# DSO_IO.net
KiCad netlist of a schematic drawn in Altium Designer
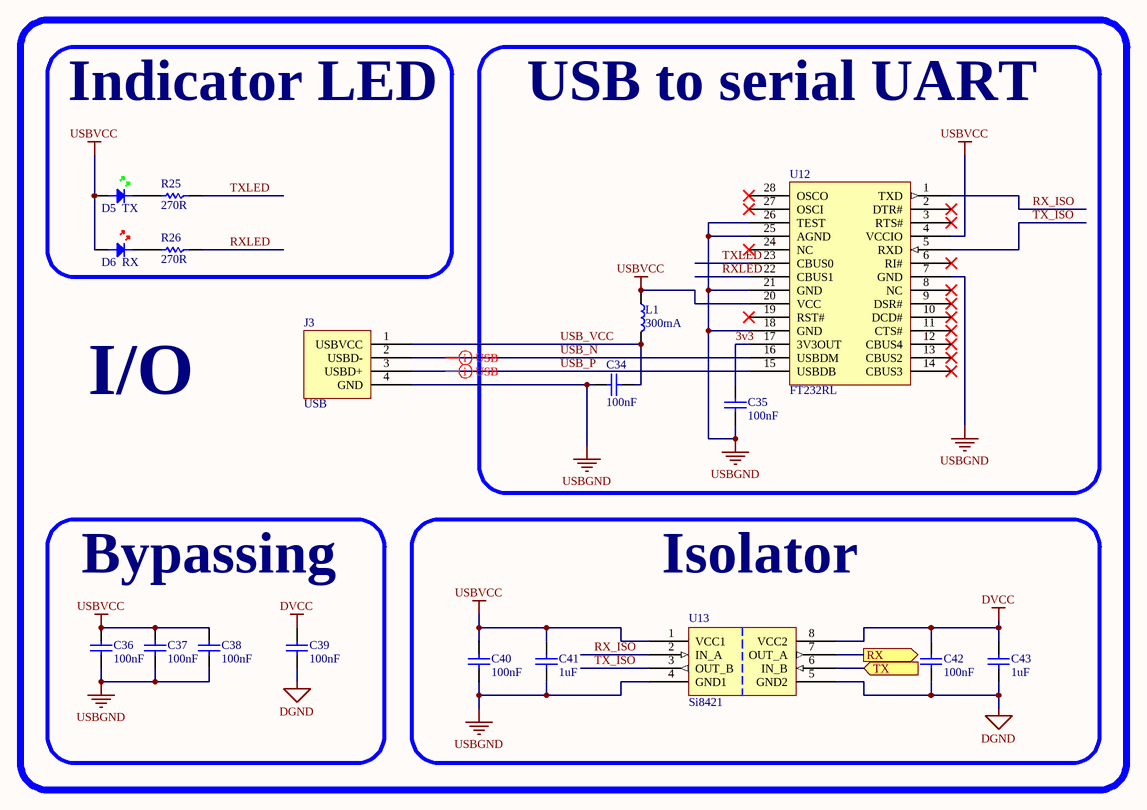
[diagram p0: DSO_IO.SchDoc]

(export (version "E")
  (design (tool "Eeschema 10.0.6"))
  (components
    (comp (ref "C34")
      (value "100nF")
      (footprint "0805C")
      (description "Capacitor")
      (fields (field (name "REVIEWED BY") "RM - 2018/08/05"))
      (libsource (lib "DSO") (part "C"))
    )
    (comp (ref "C35")
      (value "100nF")
      (footprint "0805C")
      (description "Capacitor")
      (fields (field (name "REVIEWED BY") "RM - 2018/08/05"))
      (libsource (lib "DSO") (part "C"))
    )
    (comp (ref "C36")
      (value "100nF")
      (footprint "0805C")
      (description "Capacitor")
      (fields (field (name "REVIEWED BY") "RM - 2018/08/05"))
      (libsource (lib "DSO") (part "C"))
    )
    (comp (ref "C37")
      (value "100nF")
      (footprint "0805C")
      (description "Capacitor")
      (fields (field (name "REVIEWED BY") "RM - 2018/08/05"))
      (libsource (lib "DSO") (part "C"))
    )
    (comp (ref "C38")
      (value "100nF")
      (footprint "0805C")
      (description "Capacitor")
      (fields (field (name "REVIEWED BY") "RM - 2018/08/05"))
      (libsource (lib "DSO") (part "C"))
    )
    (comp (ref "C39")
      (value "100nF")
      (footprint "0805C")
      (description "Capacitor")
      (fields (field (name "REVIEWED BY") "RM - 2018/08/05"))
      (libsource (lib "DSO") (part "C"))
    )
    (comp (ref "C40")
      (value "100nF")
      (footprint "0805C")
      (description "Capacitor")
      (fields (field (name "REVIEWED BY") "RM - 2018/08/05"))
      (libsource (lib "DSO") (part "C"))
    )
    (comp (ref "C41")
      (value "1uF")
      (footprint "0805C")
      (description "Capacitor")
      (fields (field (name "REVIEWED BY") "RM - 2018/08/05"))
      (libsource (lib "DSO") (part "C"))
    )
    (comp (ref "C42")
      (value "100nF")
      (footprint "0805C")
      (description "Capacitor")
      (fields (field (name "REVIEWED BY") "RM - 2018/08/05"))
      (libsource (lib "DSO") (part "C"))
    )
    (comp (ref "C43")
      (value "1uF")
      (footprint "0805C")
      (description "Capacitor")
      (fields (field (name "REVIEWED BY") "RM - 2018/08/05"))
      (libsource (lib "DSO") (part "C"))
    )
    (comp (ref "D5")
      (value "TX")
      (footprint "0805D-GREEN")
      (description "Light Emitting Diode")
      (fields (field (name "REVIEWED BY") "RM - 2018/08/05"))
      (libsource (lib "DSO") (part "LED GREEN"))
    )
    (comp (ref "D6")
      (value "RX")
      (footprint "0805D-RED")
      (description "Light Emitting Diode")
      (fields (field (name "REVIEWED BY") "RM - 2018/08/05"))
      (libsource (lib "DSO") (part "LED RED"))
    )
    (comp (ref "J3")
      (value "USB")
      (footprint "USBPLUG")
      (description "USB B Type Connector")
      (fields (field (name "REVIEWED BY") "RM - 2018/08/05"))
      (libsource (lib "DSO") (part "USBPLUG"))
    )
    (comp (ref "L1")
      (value "300mA")
      (footprint "0805")
      (description "Inductor")
      (fields (field (name "REVIEWED BY") "RM - 2018/08/05"))
      (libsource (lib "DSO") (part "I"))
    )
    (comp (ref "R25")
      (value "270R")
      (footprint "0805")
      (description "Resistor")
      (fields (field (name "REVIEWED BY") "RM - 2018/08/05"))
      (libsource (lib "DSO") (part "R"))
    )
    (comp (ref "R26")
      (value "270R")
      (footprint "0805")
      (description "Resistor")
      (fields (field (name "REVIEWED BY") "RM - 2018/08/05"))
      (libsource (lib "DSO") (part "R"))
    )
    (comp (ref "U12")
      (value "FT232RL")
      (footprint "SSOP-28")
      (description "USB to Serial bridge")
      (fields (field (name "REVIEWED BY") "RM - 2018/08/05"))
      (libsource (lib "DSO") (part "FT232RL"))
    )
    (comp (ref "U13")
      (value "Si8421")
      (footprint "SOIC-8")
      (description "Dual Channel Digital Isolator Both Ways")
      (fields (field (name "REVIEWED BY") "RM - 2018/08/05"))
      (libsource (lib "DSO") (part "Si8421"))
    )
  )
  (nets
    (net (code "1") (name "/3v3") (class "Default")
      (node (ref "C35") (pin "1") (pinfunction "1_1") (pintype "passive"))
      (node (ref "U12") (pin "17") (pinfunction "3V3OUT_17") (pintype "passive"))
    )
    (net (code "2") (name "/RX") (class "Default")
      (node (ref "U13") (pin "7") (pinfunction "OUT_A_7") (pintype "output"))
    )
    (net (code "3") (name "/RXLED") (class "Default")
      (node (ref "R26") (pin "1") (pintype "passive"))
      (node (ref "U12") (pin "22") (pinfunction "CBUS1_22") (pintype "passive"))
    )
    (net (code "4") (name "/RX_ISO") (class "Default")
      (node (ref "U12") (pin "1") (pinfunction "TXD_1") (pintype "output"))
      (node (ref "U13") (pin "2") (pinfunction "IN_A_2") (pintype "input"))
    )
    (net (code "5") (name "/TX") (class "Default")
      (node (ref "U13") (pin "6") (pinfunction "IN_B_6") (pintype "input"))
    )
    (net (code "6") (name "/TXLED") (class "Default")
      (node (ref "R25") (pin "1") (pintype "passive"))
      (node (ref "U12") (pin "23") (pinfunction "CBUS0_23") (pintype "passive"))
    )
    (net (code "7") (name "/TX_ISO") (class "Default")
      (node (ref "U12") (pin "5") (pinfunction "RXD_5") (pintype "input"))
      (node (ref "U13") (pin "3") (pinfunction "OUT_B_3") (pintype "output"))
    )
    (net (code "8") (name "/USB_N") (class "Default")
      (node (ref "J3") (pin "2") (pinfunction "USBD-_2") (pintype "passive"))
      (node (ref "U12") (pin "16") (pinfunction "USBDM_16") (pintype "passive"))
    )
    (net (code "9") (name "/USB_P") (class "Default")
      (node (ref "J3") (pin "3") (pinfunction "USBD+_3") (pintype "passive"))
      (node (ref "U12") (pin "15") (pinfunction "USBDB_15") (pintype "passive"))
    )
    (net (code "10") (name "/USB_VCC") (class "Default")
      (node (ref "C34") (pin "1") (pinfunction "1_1") (pintype "passive"))
      (node (ref "J3") (pin "1") (pinfunction "USBVCC_1") (pintype "passive"))
      (node (ref "L1") (pin "2") (pinfunction "2_2") (pintype "passive"))
    )
    (net (code "11") (name "DGND") (class "Default")
      (node (ref "C39") (pin "2") (pinfunction "2_2") (pintype "passive"))
      (node (ref "C42") (pin "2") (pinfunction "2_2") (pintype "passive"))
      (node (ref "C43") (pin "2") (pinfunction "2_2") (pintype "passive"))
      (node (ref "U13") (pin "5") (pinfunction "GND2_5") (pintype "passive"))
    )
    (net (code "12") (name "DVCC") (class "Default")
      (node (ref "C39") (pin "1") (pinfunction "1_1") (pintype "passive"))
      (node (ref "C42") (pin "1") (pinfunction "1_1") (pintype "passive"))
      (node (ref "C43") (pin "1") (pinfunction "1_1") (pintype "passive"))
      (node (ref "U13") (pin "8") (pinfunction "VCC2_8") (pintype "passive"))
    )
    (net (code "13") (name "Net-(D5-PadK)") (class "Default")
      (node (ref "D5") (pin "K") (pinfunction "K_K") (pintype "passive"))
      (node (ref "R25") (pin "2") (pintype "passive"))
    )
    (net (code "14") (name "Net-(D6-PadK)") (class "Default")
      (node (ref "D6") (pin "K") (pinfunction "K_K") (pintype "passive"))
      (node (ref "R26") (pin "2") (pintype "passive"))
    )
    (net (code "15") (name "USBGND") (class "Default")
      (node (ref "C34") (pin "2") (pinfunction "2_2") (pintype "passive"))
      (node (ref "C35") (pin "2") (pinfunction "2_2") (pintype "passive"))
      (node (ref "C36") (pin "2") (pinfunction "2_2") (pintype "passive"))
      (node (ref "C37") (pin "2") (pinfunction "2_2") (pintype "passive"))
      (node (ref "C38") (pin "2") (pinfunction "2_2") (pintype "passive"))
      (node (ref "C40") (pin "2") (pinfunction "2_2") (pintype "passive"))
      (node (ref "C41") (pin "2") (pinfunction "2_2") (pintype "passive"))
      (node (ref "J3") (pin "4") (pinfunction "GND_4") (pintype "passive"))
      (node (ref "U12") (pin "18") (pinfunction "GND_18") (pintype "passive"))
      (node (ref "U12") (pin "21") (pinfunction "GND_21") (pintype "passive"))
      (node (ref "U12") (pin "25") (pinfunction "AGND_25") (pintype "passive"))
      (node (ref "U12") (pin "26") (pinfunction "TEST_26") (pintype "passive"))
      (node (ref "U12") (pin "7") (pinfunction "GND_7") (pintype "passive"))
      (node (ref "U13") (pin "4") (pinfunction "GND1_4") (pintype "passive"))
    )
    (net (code "16") (name "USBVCC") (class "Default")
      (node (ref "C36") (pin "1") (pinfunction "1_1") (pintype "passive"))
      (node (ref "C37") (pin "1") (pinfunction "1_1") (pintype "passive"))
      (node (ref "C38") (pin "1") (pinfunction "1_1") (pintype "passive"))
      (node (ref "C40") (pin "1") (pinfunction "1_1") (pintype "passive"))
      (node (ref "C41") (pin "1") (pinfunction "1_1") (pintype "passive"))
      (node (ref "D5") (pin "A") (pinfunction "A_A") (pintype "passive"))
      (node (ref "D6") (pin "A") (pinfunction "A_A") (pintype "passive"))
      (node (ref "L1") (pin "1") (pinfunction "1_1") (pintype "passive"))
      (node (ref "U12") (pin "20") (pinfunction "VCC_20") (pintype "passive"))
      (node (ref "U12") (pin "4") (pinfunction "VCCIO_4") (pintype "passive"))
      (node (ref "U13") (pin "1") (pinfunction "VCC1_1") (pintype "passive"))
    )
    (net (code "17") (name "unconnected-(U12-CBUS2-Pad13)") (class "Default")
      (node (ref "U12") (pin "13") (pinfunction "CBUS2_13") (pintype "passive+no_connect"))
    )
    (net (code "18") (name "unconnected-(U12-CBUS3-Pad14)") (class "Default")
      (node (ref "U12") (pin "14") (pinfunction "CBUS3_14") (pintype "passive+no_connect"))
    )
    (net (code "19") (name "unconnected-(U12-CBUS4-Pad12)") (class "Default")
      (node (ref "U12") (pin "12") (pinfunction "CBUS4_12") (pintype "passive+no_connect"))
    )
    (net (code "20") (name "unconnected-(U12-CTS#-Pad11)") (class "Default")
      (node (ref "U12") (pin "11") (pinfunction "CTS#_11") (pintype "passive+no_connect"))
    )
    (net (code "21") (name "unconnected-(U12-DCD#-Pad10)") (class "Default")
      (node (ref "U12") (pin "10") (pinfunction "DCD#_10") (pintype "passive+no_connect"))
    )
    (net (code "22") (name "unconnected-(U12-DSR#-Pad9)") (class "Default")
      (node (ref "U12") (pin "9") (pinfunction "DSR#_9") (pintype "passive+no_connect"))
    )
    (net (code "23") (name "unconnected-(U12-DTR#-Pad2)") (class "Default")
      (node (ref "U12") (pin "2") (pinfunction "DTR#_2") (pintype "passive+no_connect"))
    )
    (net (code "24") (name "unconnected-(U12-NC-Pad8)") (class "Default")
      (node (ref "U12") (pin "8") (pinfunction "NC_8") (pintype "passive+no_connect"))
    )
    (net (code "25") (name "unconnected-(U12-NC-Pad24)") (class "Default")
      (node (ref "U12") (pin "24") (pinfunction "NC_24") (pintype "passive+no_connect"))
    )
    (net (code "26") (name "unconnected-(U12-OSCI-Pad27)") (class "Default")
      (node (ref "U12") (pin "27") (pinfunction "OSCI_27") (pintype "passive+no_connect"))
    )
    (net (code "27") (name "unconnected-(U12-OSCO-Pad28)") (class "Default")
      (node (ref "U12") (pin "28") (pinfunction "OSCO_28") (pintype "passive+no_connect"))
    )
    (net (code "28") (name "unconnected-(U12-RI#-Pad6)") (class "Default")
      (node (ref "U12") (pin "6") (pinfunction "RI#_6") (pintype "passive+no_connect"))
    )
    (net (code "29") (name "unconnected-(U12-RST#-Pad19)") (class "Default")
      (node (ref "U12") (pin "19") (pinfunction "RST#_19") (pintype "passive+no_connect"))
    )
    (net (code "30") (name "unconnected-(U12-RTS#-Pad3)") (class "Default")
      (node (ref "U12") (pin "3") (pinfunction "RTS#_3") (pintype "passive+no_connect"))
    )
  )
)
